# Battery_board_V4_0.net
KiCad netlist of a schematic drawn in EAGLE
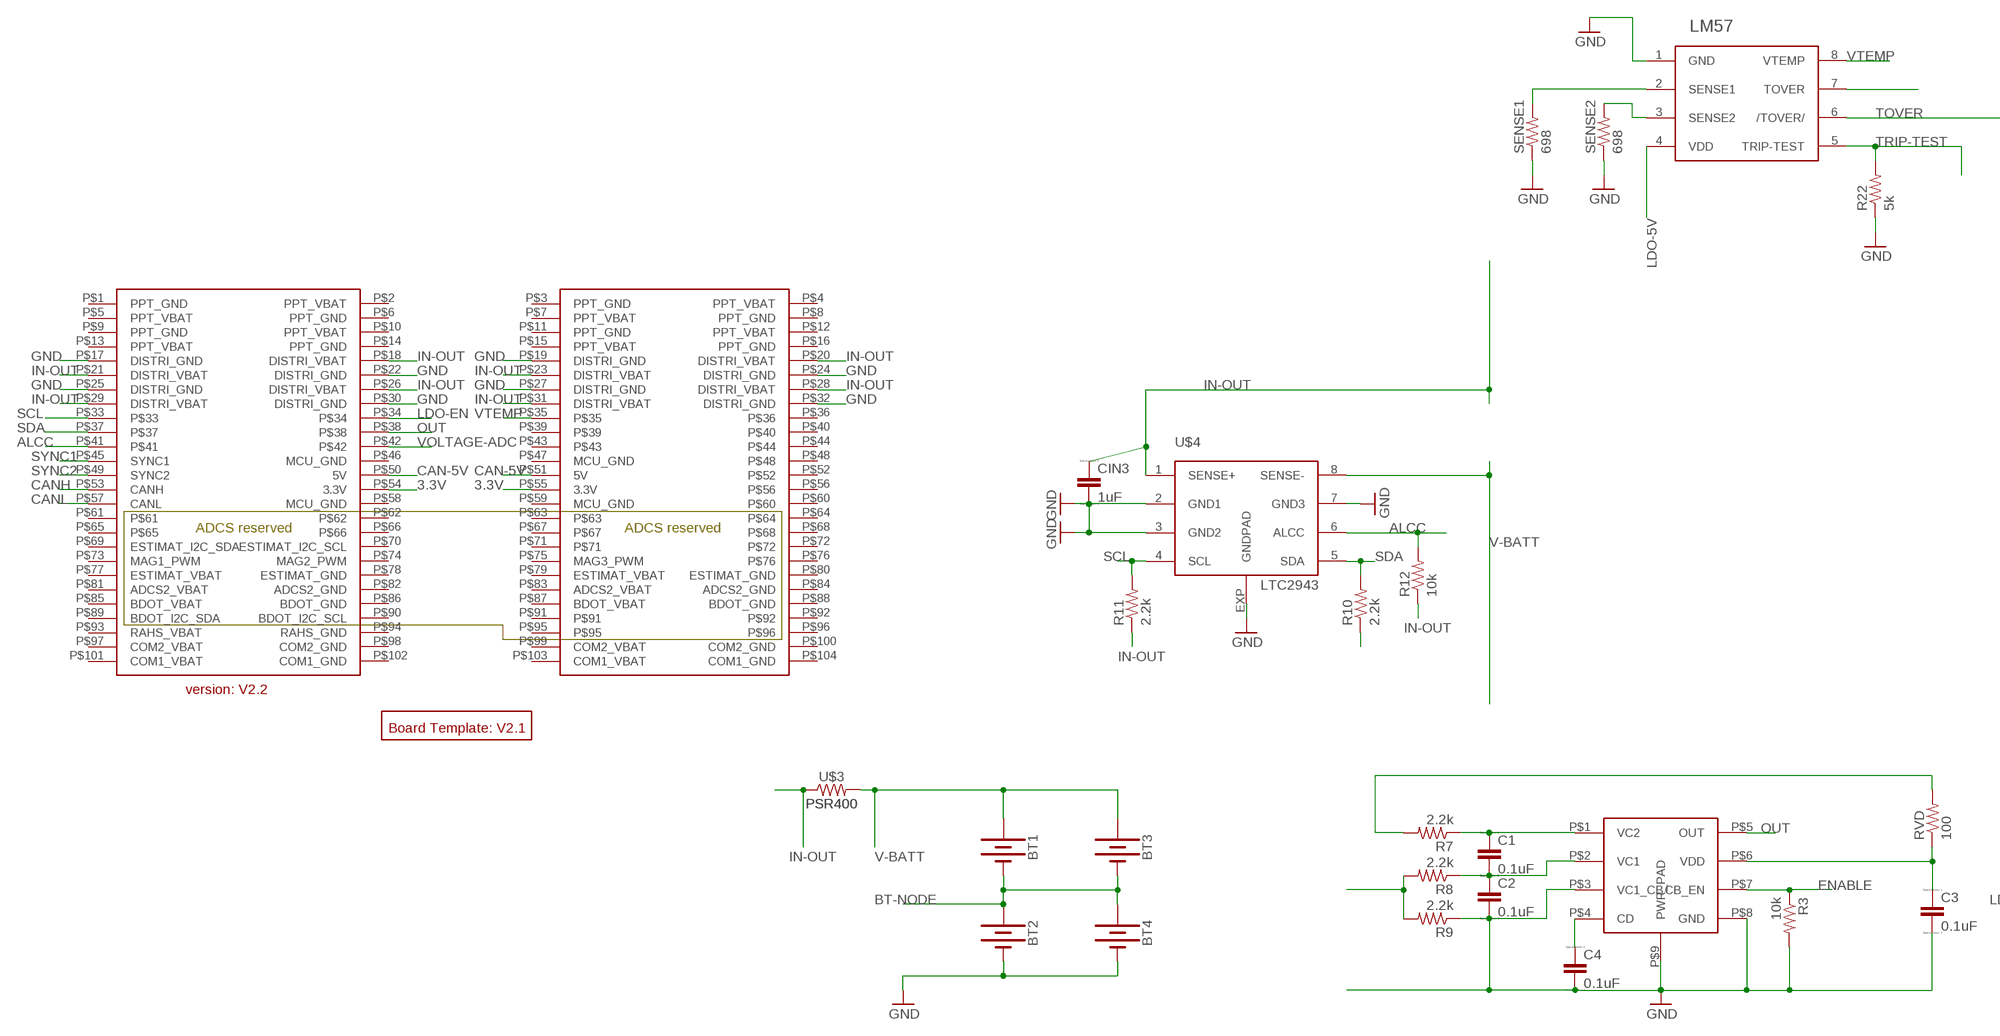
[diagram p0: schematic, sheet 1, part 1 of 2]
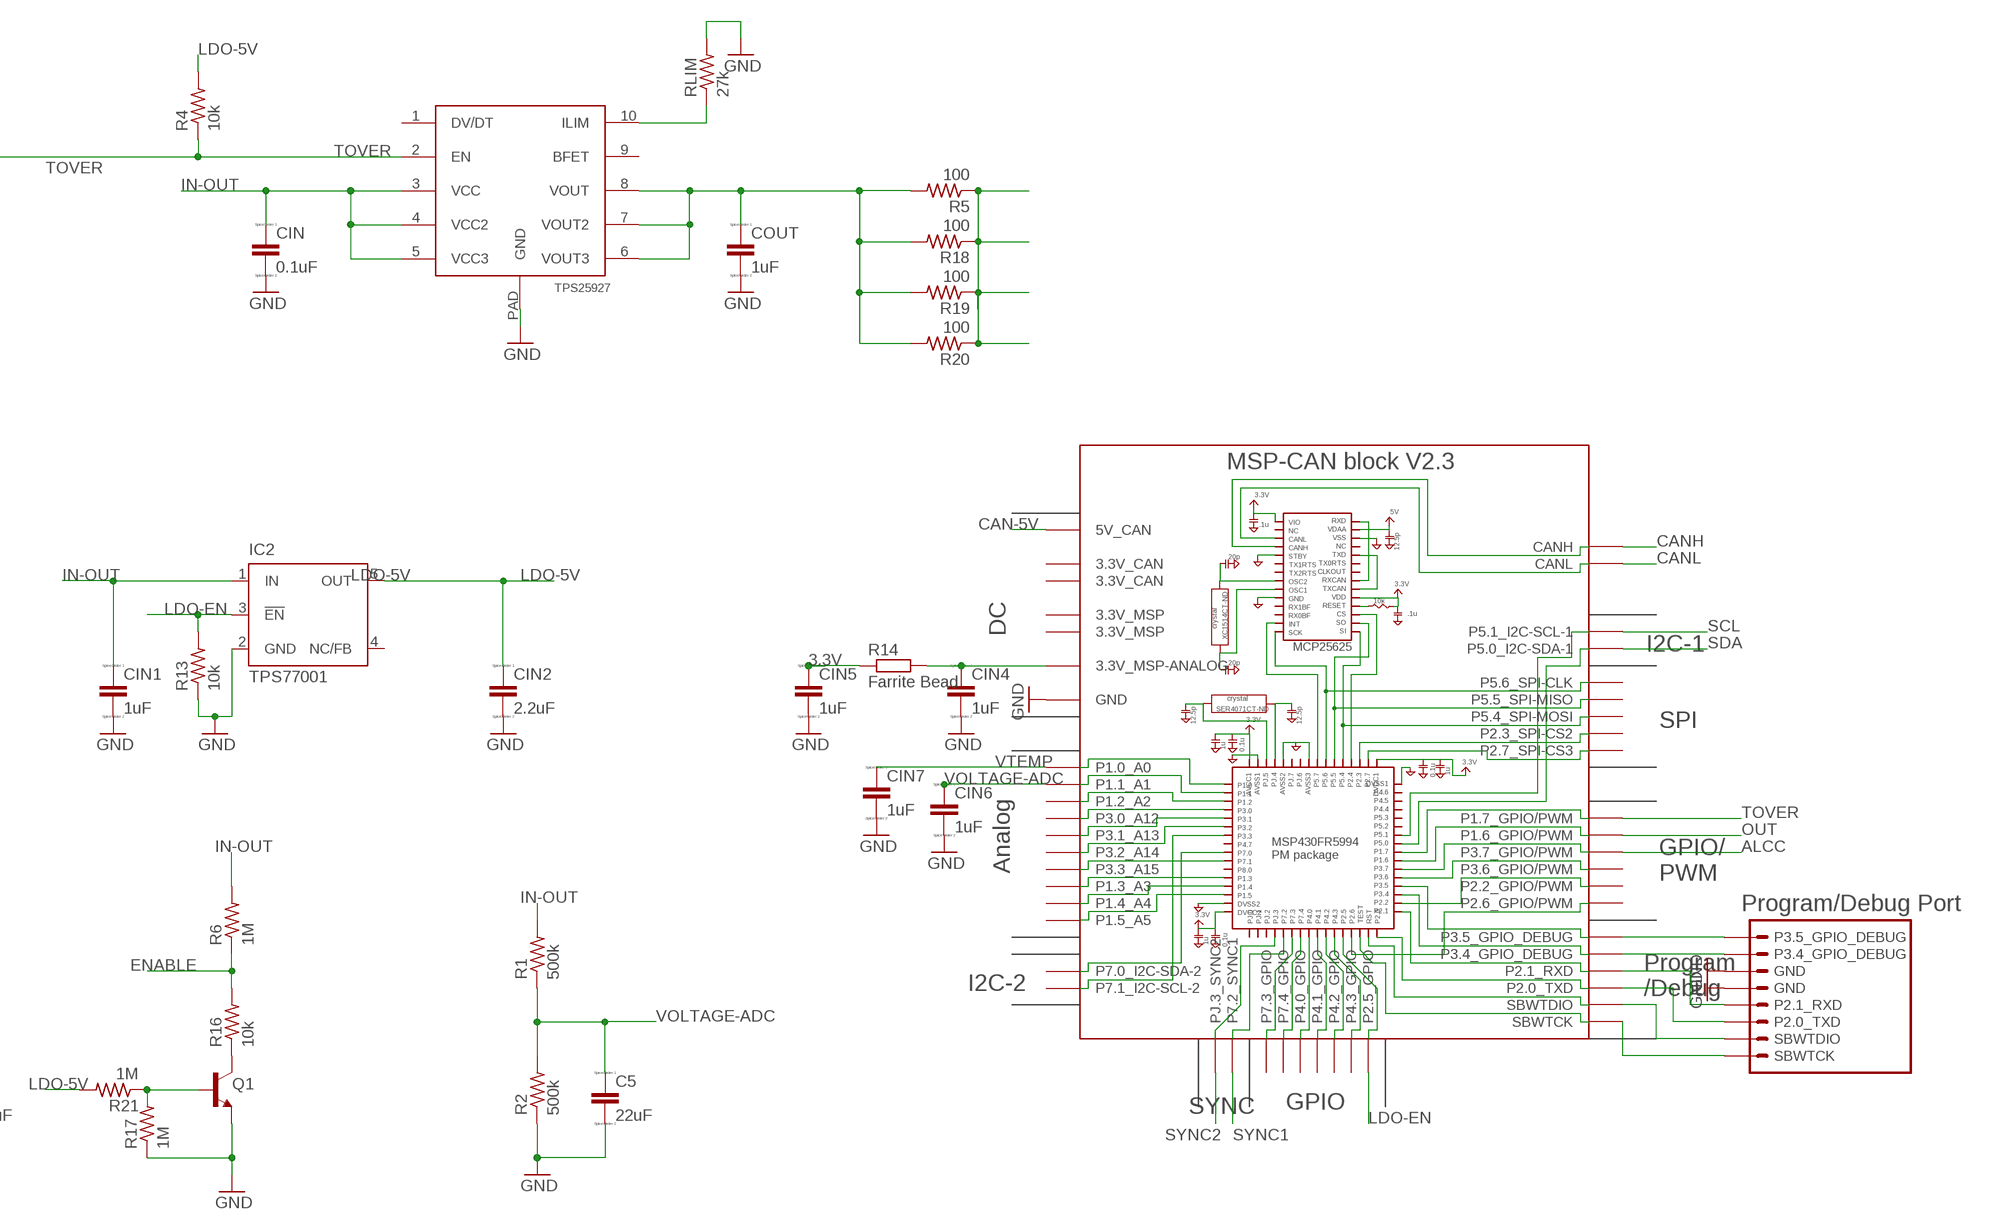
[diagram p1: schematic, sheet 1, part 2 of 2]

(export (version "E")
  (design (tool "Eeschema 10.0.6"))
  (components
    (comp (ref "BT1")
      (value "BATTERY-18650")
      (footprint "eagle-import:BATTERY_18650-HOLDER")
      (libsource (lib "eagle-import") (part "BATTERY-18650"))
    )
    (comp (ref "BT2")
      (value "BATTERY-18650")
      (footprint "eagle-import:BATTERY_18650-HOLDER")
      (libsource (lib "eagle-import") (part "BATTERY-18650"))
    )
    (comp (ref "BT3")
      (value "BATTERY-18650")
      (footprint "eagle-import:BATTERY_18650-HOLDER")
      (libsource (lib "eagle-import") (part "BATTERY-18650"))
    )
    (comp (ref "BT4")
      (value "BATTERY-18650")
      (footprint "eagle-import:BATTERY_18650-HOLDER")
      (libsource (lib "eagle-import") (part "BATTERY-18650"))
    )
    (comp (ref "C1")
      (value "0.1uF")
      (footprint "eagle-import:C0805")
      (libsource (lib "eagle-import") (part "C"))
    )
    (comp (ref "C2")
      (value "0.1uF")
      (footprint "eagle-import:C0805")
      (libsource (lib "eagle-import") (part "C"))
    )
    (comp (ref "C3")
      (value "0.1uF")
      (footprint "eagle-import:C0805")
      (libsource (lib "eagle-import") (part "C"))
    )
    (comp (ref "C4")
      (value "0.1uF")
      (footprint "eagle-import:C0805")
      (libsource (lib "eagle-import") (part "C"))
    )
    (comp (ref "C5")
      (value "22uF")
      (footprint "eagle-import:C1206")
      (libsource (lib "eagle-import") (part "CC1206"))
    )
    (comp (ref "CIN")
      (value "0.1uF")
      (footprint "eagle-import:C0805")
      (libsource (lib "eagle-import") (part "C"))
    )
    (comp (ref "CIN1")
      (value "1uF")
      (footprint "eagle-import:C0805")
      (libsource (lib "eagle-import") (part "C"))
    )
    (comp (ref "CIN2")
      (value "2.2uF")
      (footprint "eagle-import:C0805")
      (libsource (lib "eagle-import") (part "C"))
    )
    (comp (ref "CIN3")
      (value "1uF")
      (footprint "eagle-import:C0805")
      (libsource (lib "eagle-import") (part "C"))
    )
    (comp (ref "CIN4")
      (value "1uF")
      (footprint "eagle-import:C0805")
      (libsource (lib "eagle-import") (part "C"))
    )
    (comp (ref "CIN5")
      (value "1uF")
      (footprint "eagle-import:C0805")
      (libsource (lib "eagle-import") (part "C"))
    )
    (comp (ref "CIN6")
      (value "1uF")
      (footprint "eagle-import:C0805")
      (libsource (lib "eagle-import") (part "C"))
    )
    (comp (ref "CIN7")
      (value "1uF")
      (footprint "eagle-import:C0805")
      (libsource (lib "eagle-import") (part "C"))
    )
    (comp (ref "COUT")
      (value "1uF")
      (footprint "eagle-import:C0805")
      (libsource (lib "eagle-import") (part "C"))
    )
    (comp (ref "IC2")
      (value "TPS77001")
      (footprint "eagle-import:SOT23-DBV")
      (fields (field (name "MF") "TEXAS INSTRUMENTS") (field (name "MPN") "TPS77001DBVT"))
      (libsource (lib "eagle-import") (part "TPS77001"))
    )
    (comp (ref "Q1")
      (value "TRANS_NPN-MMBT2222AL")
      (footprint "eagle-import:SOT23-3")
      (libsource (lib "eagle-import") (part "TRANS_NPN-MMBT2222AL"))
    )
    (comp (ref "R1")
      (value "500k")
      (footprint "eagle-import:R0805")
      (libsource (lib "eagle-import") (part "R-US_R0805"))
    )
    (comp (ref "R2")
      (value "500k")
      (footprint "eagle-import:R0805")
      (libsource (lib "eagle-import") (part "R-US_R0805"))
    )
    (comp (ref "R3")
      (value "10k")
      (footprint "eagle-import:R0805")
      (libsource (lib "eagle-import") (part "R-US_R0805"))
    )
    (comp (ref "R4")
      (value "10k")
      (footprint "eagle-import:R0805")
      (libsource (lib "eagle-import") (part "R-US_R0805"))
    )
    (comp (ref "R5")
      (value "100")
      (footprint "eagle-import:R0805")
      (libsource (lib "eagle-import") (part "R-US_R0805"))
    )
    (comp (ref "R6")
      (value "1M")
      (footprint "eagle-import:R0805")
      (libsource (lib "eagle-import") (part "R-US_R0805"))
    )
    (comp (ref "R7")
      (value "2.2k")
      (footprint "eagle-import:R0805")
      (libsource (lib "eagle-import") (part "R-US_R0805"))
    )
    (comp (ref "R8")
      (value "2.2k")
      (footprint "eagle-import:R0805")
      (libsource (lib "eagle-import") (part "R-US_R0805"))
    )
    (comp (ref "R9")
      (value "2.2k")
      (footprint "eagle-import:R0805")
      (libsource (lib "eagle-import") (part "R-US_R0805"))
    )
    (comp (ref "R10")
      (value "2.2k")
      (footprint "eagle-import:R0805")
      (libsource (lib "eagle-import") (part "R-US_R0805"))
    )
    (comp (ref "R11")
      (value "2.2k")
      (footprint "eagle-import:R0805")
      (libsource (lib "eagle-import") (part "R-US_R0805"))
    )
    (comp (ref "R12")
      (value "10k")
      (footprint "eagle-import:R0805")
      (libsource (lib "eagle-import") (part "R-US_R0805"))
    )
    (comp (ref "R13")
      (value "10k")
      (footprint "eagle-import:R0805")
      (libsource (lib "eagle-import") (part "R-US_R0805"))
    )
    (comp (ref "R14")
      (value "Farrite Bead")
      (footprint "eagle-import:R1206")
      (libsource (lib "eagle-import") (part "R-EU_R1206"))
    )
    (comp (ref "R16")
      (value "10k")
      (footprint "eagle-import:R0805")
      (libsource (lib "eagle-import") (part "R-US_R0805"))
    )
    (comp (ref "R17")
      (value "1M")
      (footprint "eagle-import:M0805")
      (libsource (lib "eagle-import") (part "R-US_M0805"))
    )
    (comp (ref "R18")
      (value "100")
      (footprint "eagle-import:R0805")
      (libsource (lib "eagle-import") (part "R-US_R0805"))
    )
    (comp (ref "R19")
      (value "100")
      (footprint "eagle-import:R0805")
      (libsource (lib "eagle-import") (part "R-US_R0805"))
    )
    (comp (ref "R20")
      (value "100")
      (footprint "eagle-import:R0805")
      (libsource (lib "eagle-import") (part "R-US_R0805"))
    )
    (comp (ref "R21")
      (value "1M")
      (footprint "eagle-import:M0805")
      (libsource (lib "eagle-import") (part "R-US_M0805"))
    )
    (comp (ref "R22")
      (value "5k")
      (footprint "eagle-import:R0805")
      (libsource (lib "eagle-import") (part "R-US_R0805"))
    )
    (comp (ref "RLIM")
      (value "27k")
      (footprint "eagle-import:R0805")
      (libsource (lib "eagle-import") (part "R-US_R0805"))
    )
    (comp (ref "RVD")
      (value "100")
      (footprint "eagle-import:R0805")
      (libsource (lib "eagle-import") (part "R-US_R0805"))
    )
    (comp (ref "SENSE1")
      (value "698")
      (footprint "eagle-import:R0805")
      (libsource (lib "eagle-import") (part "R-US_R0805"))
    )
    (comp (ref "SENSE2")
      (value "698")
      (footprint "eagle-import:R0805")
      (libsource (lib "eagle-import") (part "R-US_R0805"))
    )
    (comp (ref "U$1")
      (value "MSP-CAN_BLOCK")
      (footprint "eagle-import:MSP-CAN_BLOCK")
      (libsource (lib "eagle-import") (part "MSP-CAN_BLOCK"))
    )
    (comp (ref "U$2")
      (value "PROGRAM/DEBUG_PORT")
      (footprint "eagle-import:1X08_CONNECTOR")
      (libsource (lib "eagle-import") (part "PROGRAM/DEBUG_PORT"))
    )
    (comp (ref "U$3")
      (value "PSR400")
      (footprint "eagle-import:PSR400")
      (libsource (lib "eagle-import") (part "PSR400"))
    )
    (comp (ref "U$4")
      (value "LTC2943")
      (footprint "eagle-import:DFN8(3X3)LT")
      (libsource (lib "eagle-import") (part "LTC2943"))
    )
    (comp (ref "U$5")
      (value "TPS252927")
      (footprint "eagle-import:VSON10")
      (libsource (lib "eagle-import") (part "TPS252927"))
    )
    (comp (ref "U$6")
      (value "LM57")
      (footprint "eagle-import:TSSOP-8")
      (libsource (lib "eagle-import") (part "LM57"))
    )
    (comp (ref "U$7")
      (value "2X26_CONNECTOR_(V2.2)")
      (footprint "eagle-import:4X26_CONNECTOR_(V2.2)")
      (libsource (lib "eagle-import") (part "2X26_CONNECTOR_(V2.2)"))
    )
    (comp (ref "U$8")
      (value "BQ29209")
      (footprint "eagle-import:VSON8")
      (libsource (lib "eagle-import") (part "BQ29209"))
    )
    (comp (ref "U$9")
      (value "BOARD_TEMPLATE_(V2.1)")
      (footprint "eagle-import:BOARD_TEMPLATE_(V2.1)")
      (libsource (lib "eagle-import") (part "BOARD_TEMPLATE_(V2.1)"))
    )
  )
  (nets
    (net (code "1") (name "/3.3V") (class "Default")
      (node (ref "CIN5") (pin "1") (pinfunction "1_1") (pintype "passive"))
      (node (ref "R14") (pin "1") (pinfunction "1_1") (pintype "passive"))
      (node (ref "U$7") (pin "P$54") (pinfunction "3.3V_P$54") (pintype "bidirectional"))
      (node (ref "U$7") (pin "P$55") (pinfunction "3.3V_P$55") (pintype "bidirectional"))
    )
    (net (code "2") (name "/ALCC") (class "Default")
      (node (ref "R12") (pin "2") (pinfunction "2_2") (pintype "passive"))
      (node (ref "U$1") (pin "P3.7_GPIO/PWM") (pinfunction "P3.7_GPIO/PWM_P3.7_GPIO/PWM") (pintype "bidirectional"))
      (node (ref "U$4") (pin "6") (pinfunction "ALCC_6") (pintype "bidirectional"))
      (node (ref "U$7") (pin "P$41") (pinfunction "P$41_P$41") (pintype "bidirectional"))
    )
    (net (code "3") (name "/BT-NODE") (class "Default")
      (node (ref "BT1") (pin "GND@1") (pinfunction "-_GND@1") (pintype "power_in"))
      (node (ref "BT2") (pin "PWR@1") (pinfunction "+_PWR@1") (pintype "power_in"))
      (node (ref "BT3") (pin "GND@1") (pinfunction "-_GND@1") (pintype "power_in"))
      (node (ref "BT4") (pin "PWR@1") (pinfunction "+_PWR@1") (pintype "power_in"))
      (node (ref "R8") (pin "2") (pinfunction "2_2") (pintype "passive"))
      (node (ref "R9") (pin "2") (pinfunction "2_2") (pintype "passive"))
    )
    (net (code "4") (name "/CAN-5V") (class "Default")
      (node (ref "U$1") (pin "5V") (pinfunction "5V_CAN_5V") (pintype "bidirectional"))
      (node (ref "U$7") (pin "P$50") (pinfunction "5V_P$50") (pintype "bidirectional"))
      (node (ref "U$7") (pin "P$51") (pinfunction "5V_P$51") (pintype "bidirectional"))
    )
    (net (code "5") (name "/CANH") (class "Default")
      (node (ref "U$1") (pin "CANH") (pinfunction "CANH_CANH") (pintype "bidirectional"))
      (node (ref "U$7") (pin "P$53") (pinfunction "CANH_P$53") (pintype "bidirectional"))
    )
    (net (code "6") (name "/CANL") (class "Default")
      (node (ref "U$1") (pin "CANL") (pinfunction "CANL_CANL") (pintype "bidirectional"))
      (node (ref "U$7") (pin "P$57") (pinfunction "CANL_P$57") (pintype "bidirectional"))
    )
    (net (code "7") (name "/ENABLE") (class "Default")
      (node (ref "R16") (pin "2") (pinfunction "2_2") (pintype "passive"))
      (node (ref "R3") (pin "1") (pinfunction "1_1") (pintype "passive"))
      (node (ref "R6") (pin "1") (pinfunction "1_1") (pintype "passive"))
      (node (ref "U$8") (pin "P$7") (pinfunction "CB_EN_P$7") (pintype "bidirectional"))
    )
    (net (code "8") (name "/IN-OUT") (class "Default")
      (node (ref "CIN") (pin "1") (pinfunction "1_1") (pintype "passive"))
      (node (ref "CIN1") (pin "1") (pinfunction "1_1") (pintype "passive"))
      (node (ref "CIN3") (pin "1") (pinfunction "1_1") (pintype "passive"))
      (node (ref "IC2") (pin "1") (pinfunction "IN_1") (pintype "input"))
      (node (ref "R1") (pin "2") (pinfunction "2_2") (pintype "passive"))
      (node (ref "R10") (pin "1") (pinfunction "1_1") (pintype "passive"))
      (node (ref "R11") (pin "1") (pinfunction "1_1") (pintype "passive"))
      (node (ref "R12") (pin "1") (pinfunction "1_1") (pintype "passive"))
      (node (ref "R6") (pin "2") (pinfunction "2_2") (pintype "passive"))
      (node (ref "U$3") (pin "P$1") (pinfunction "1_P$1") (pintype "passive"))
      (node (ref "U$4") (pin "1") (pinfunction "SENSE+_1") (pintype "bidirectional"))
      (node (ref "U$5") (pin "3") (pinfunction "VCC_3") (pintype "bidirectional"))
      (node (ref "U$5") (pin "4") (pinfunction "VCC2_4") (pintype "bidirectional"))
      (node (ref "U$5") (pin "5") (pinfunction "VCC3_5") (pintype "bidirectional"))
      (node (ref "U$7") (pin "P$18") (pinfunction "DISTRI_VBAT_P$18") (pintype "bidirectional"))
      (node (ref "U$7") (pin "P$20") (pinfunction "DISTRI_VBAT_P$20") (pintype "bidirectional"))
      (node (ref "U$7") (pin "P$21") (pinfunction "DISTRI_VBAT_P$21") (pintype "bidirectional"))
      (node (ref "U$7") (pin "P$23") (pinfunction "DISTRI_VBAT_P$23") (pintype "bidirectional"))
      (node (ref "U$7") (pin "P$26") (pinfunction "DISTRI_VBAT_P$26") (pintype "bidirectional"))
      (node (ref "U$7") (pin "P$28") (pinfunction "DISTRI_VBAT_P$28") (pintype "bidirectional"))
      (node (ref "U$7") (pin "P$29") (pinfunction "DISTRI_VBAT_P$29") (pintype "bidirectional"))
      (node (ref "U$7") (pin "P$31") (pinfunction "DISTRI_VBAT_P$31") (pintype "bidirectional"))
    )
    (net (code "9") (name "/LDO-5V") (class "Default")
      (node (ref "CIN2") (pin "1") (pinfunction "1_1") (pintype "passive"))
      (node (ref "IC2") (pin "5") (pinfunction "OUT_5") (pintype "passive"))
      (node (ref "R21") (pin "2") (pinfunction "2_2") (pintype "passive"))
      (node (ref "R4") (pin "2") (pinfunction "2_2") (pintype "passive"))
      (node (ref "U$6") (pin "4") (pinfunction "VDD_4") (pintype "bidirectional"))
    )
    (net (code "10") (name "/LDO-EN") (class "Default")
      (node (ref "IC2") (pin "3") (pinfunction "~{EN}_3") (pintype "input"))
      (node (ref "R13") (pin "2") (pinfunction "2_2") (pintype "passive"))
      (node (ref "U$1") (pin "P2.5_GPIO") (pinfunction "P2.5_GPIO_P2.5_GPIO") (pintype "bidirectional"))
      (node (ref "U$7") (pin "P$34") (pinfunction "P$34_P$34") (pintype "bidirectional"))
    )
    (net (code "11") (name "/OUT") (class "Default")
      (node (ref "U$1") (pin "P1.6_GPIO/PWM") (pinfunction "P1.6_GPIO/PWM_P1.6_GPIO/PWM") (pintype "bidirectional"))
      (node (ref "U$7") (pin "P$38") (pinfunction "P$38_P$38") (pintype "bidirectional"))
      (node (ref "U$8") (pin "P$5") (pinfunction "OUT_P$5") (pintype "bidirectional"))
    )
    (net (code "12") (name "/SCL") (class "Default")
      (node (ref "R11") (pin "2") (pinfunction "2_2") (pintype "passive"))
      (node (ref "U$1") (pin "P5.1_I2C-SCL-1") (pinfunction "P5.1_I2C-SCL-1_P5.1_I2C-SCL-1") (pintype "bidirectional"))
      (node (ref "U$4") (pin "4") (pinfunction "SCL_4") (pintype "bidirectional"))
      (node (ref "U$7") (pin "P$33") (pinfunction "P$33_P$33") (pintype "bidirectional"))
    )
    (net (code "13") (name "/SDA") (class "Default")
      (node (ref "R10") (pin "2") (pinfunction "2_2") (pintype "passive"))
      (node (ref "U$1") (pin "P5.0_I2C-SDA-1") (pinfunction "P5.0_I2C-SDA-1_P5.0_I2C-SDA-1") (pintype "bidirectional"))
      (node (ref "U$4") (pin "5") (pinfunction "SDA_5") (pintype "bidirectional"))
      (node (ref "U$7") (pin "P$37") (pinfunction "P$37_P$37") (pintype "bidirectional"))
    )
    (net (code "14") (name "/SYNC1") (class "Default")
      (node (ref "U$1") (pin "P7.2_SYNC1") (pinfunction "P7.2_SYNC1_P7.2_SYNC1") (pintype "bidirectional"))
      (node (ref "U$7") (pin "P$45") (pinfunction "SYNC1_P$45") (pintype "bidirectional"))
    )
    (net (code "15") (name "/SYNC2") (class "Default")
      (node (ref "U$1") (pin "PJ.3_SYNC2") (pinfunction "PJ.3_SYNC2_PJ.3_SYNC2") (pintype "bidirectional"))
      (node (ref "U$7") (pin "P$49") (pinfunction "SYNC2_P$49") (pintype "bidirectional"))
    )
    (net (code "16") (name "/TOVER") (class "Default")
      (node (ref "R4") (pin "1") (pinfunction "1_1") (pintype "passive"))
      (node (ref "U$1") (pin "P1.7_GPIO/PWM") (pinfunction "P1.7_GPIO/PWM_P1.7_GPIO/PWM") (pintype "bidirectional"))
      (node (ref "U$5") (pin "2") (pinfunction "EN_2") (pintype "bidirectional"))
      (node (ref "U$6") (pin "6") (pinfunction "/TOVER/_6") (pintype "bidirectional"))
    )
    (net (code "17") (name "/TRIP-TEST") (class "Default")
      (node (ref "R22") (pin "2") (pinfunction "2_2") (pintype "passive"))
      (node (ref "U$6") (pin "5") (pinfunction "TRIP-TEST_5") (pintype "bidirectional"))
    )
    (net (code "18") (name "/V-BATT") (class "Default")
      (node (ref "BT1") (pin "PWR@1") (pinfunction "+_PWR@1") (pintype "power_in"))
      (node (ref "BT3") (pin "PWR@1") (pinfunction "+_PWR@1") (pintype "power_in"))
      (node (ref "R7") (pin "2") (pinfunction "2_2") (pintype "passive"))
      (node (ref "RVD") (pin "2") (pinfunction "2_2") (pintype "passive"))
      (node (ref "U$3") (pin "P$2") (pinfunction "2_P$2") (pintype "passive"))
      (node (ref "U$4") (pin "8") (pinfunction "SENSE-_8") (pintype "bidirectional"))
    )
    (net (code "19") (name "/VOLTAGE-ADC") (class "Default")
      (node (ref "C5") (pin "1") (pinfunction "1_1") (pintype "passive"))
      (node (ref "CIN6") (pin "1") (pinfunction "1_1") (pintype "passive"))
      (node (ref "R1") (pin "1") (pinfunction "1_1") (pintype "passive"))
      (node (ref "R2") (pin "2") (pinfunction "2_2") (pintype "passive"))
      (node (ref "U$1") (pin "P1.1_A1") (pinfunction "P1.1_A1_P1.1_A1") (pintype "bidirectional"))
      (node (ref "U$7") (pin "P$42") (pinfunction "P$42_P$42") (pintype "bidirectional"))
    )
    (net (code "20") (name "/VTEMP") (class "Default")
      (node (ref "CIN7") (pin "1") (pinfunction "1_1") (pintype "passive"))
      (node (ref "U$1") (pin "P1.0_A0") (pinfunction "P1.0_A0_P1.0_A0") (pintype "bidirectional"))
      (node (ref "U$6") (pin "8") (pinfunction "VTEMP_8") (pintype "bidirectional"))
      (node (ref "U$7") (pin "P$35") (pinfunction "P$35_P$35") (pintype "bidirectional"))
    )
    (net (code "21") (name "GND") (class "Default")
      (node (ref "BT2") (pin "GND@1") (pinfunction "-_GND@1") (pintype "power_in"))
      (node (ref "BT4") (pin "GND@1") (pinfunction "-_GND@1") (pintype "power_in"))
      (node (ref "C2") (pin "2") (pinfunction "2_2") (pintype "passive"))
      (node (ref "C3") (pin "2") (pinfunction "2_2") (pintype "passive"))
      (node (ref "C4") (pin "2") (pinfunction "2_2") (pintype "passive"))
      (node (ref "C5") (pin "2") (pinfunction "2_2") (pintype "passive"))
      (node (ref "CIN") (pin "2") (pinfunction "2_2") (pintype "passive"))
      (node (ref "CIN1") (pin "2") (pinfunction "2_2") (pintype "passive"))
      (node (ref "CIN2") (pin "2") (pinfunction "2_2") (pintype "passive"))
      (node (ref "CIN3") (pin "2") (pinfunction "2_2") (pintype "passive"))
      (node (ref "CIN4") (pin "2") (pinfunction "2_2") (pintype "passive"))
      (node (ref "CIN5") (pin "2") (pinfunction "2_2") (pintype "passive"))
      (node (ref "CIN6") (pin "2") (pinfunction "2_2") (pintype "passive"))
      (node (ref "CIN7") (pin "2") (pinfunction "2_2") (pintype "passive"))
      (node (ref "COUT") (pin "2") (pinfunction "2_2") (pintype "passive"))
      (node (ref "IC2") (pin "2") (pinfunction "GND_2") (pintype "power_in"))
      (node (ref "Q1") (pin "2") (pinfunction "E_2") (pintype "passive"))
      (node (ref "R13") (pin "1") (pinfunction "1_1") (pintype "passive"))
      (node (ref "R17") (pin "1") (pinfunction "1_1") (pintype "passive"))
      (node (ref "R2") (pin "1") (pinfunction "1_1") (pintype "passive"))
      (node (ref "R22") (pin "1") (pinfunction "1_1") (pintype "passive"))
      (node (ref "R3") (pin "2") (pinfunction "2_2") (pintype "passive"))
      (node (ref "R9") (pin "1") (pinfunction "1_1") (pintype "passive"))
      (node (ref "RLIM") (pin "2") (pinfunction "2_2") (pintype "passive"))
      (node (ref "SENSE1") (pin "1") (pinfunction "1_1") (pintype "passive"))
      (node (ref "SENSE2") (pin "1") (pinfunction "1_1") (pintype "passive"))
      (node (ref "U$1") (pin "GND@1") (pinfunction "GND_GND@1") (pintype "bidirectional"))
      (node (ref "U$1") (pin "GND@10") (pinfunction "GND_GND@10") (pintype "bidirectional"))
      (node (ref "U$1") (pin "GND@11") (pinfunction "GND_GND@11") (pintype "bidirectional"))
      (node (ref "U$1") (pin "GND@12") (pinfunction "GND_GND@12") (pintype "bidirectional"))
      (node (ref "U$1") (pin "GND@13") (pinfunction "GND_GND@13") (pintype "bidirectional"))
      (node (ref "U$1") (pin "GND@14") (pinfunction "GND_GND@14") (pintype "bidirectional"))
      (node (ref "U$1") (pin "GND@15") (pinfunction "GND_GND@15") (pintype "bidirectional"))
      (node (ref "U$1") (pin "GND@16") (pinfunction "GND_GND@16") (pintype "bidirectional"))
      (node (ref "U$1") (pin "GND@17") (pinfunction "GND_GND@17") (pintype "bidirectional"))
      (node (ref "U$1") (pin "GND@2") (pinfunction "GND_GND@2") (pintype "bidirectional"))
      (node (ref "U$1") (pin "GND@26") (pinfunction "GND_GND@26") (pintype "bidirectional"))
      (node (ref "U$1") (pin "GND@3") (pinfunction "GND_GND@3") (pintype "bidirectional"))
      (node (ref "U$1") (pin "GND@4") (pinfunction "GND_GND@4") (pintype "bidirectional"))
      (node (ref "U$1") (pin "GND@5") (pinfunction "GND_GND@5") (pintype "bidirectional"))
      (node (ref "U$1") (pin "GND@7") (pinfunction "GND_GND@7") (pintype "bidirectional"))
      (node (ref "U$1") (pin "GND@8") (pinfunction "GND_GND@8") (pintype "bidirectional"))
      (node (ref "U$1") (pin "GND@9") (pinfunction "GND_GND@9") (pintype "bidirectional"))
      (node (ref "U$2") (pin "5") (pinfunction "GND_5") (pintype "bidirectional"))
      (node (ref "U$2") (pin "6") (pinfunction "GND_6") (pintype "bidirectional"))
      (node (ref "U$4") (pin "2") (pinfunction "GND1_2") (pintype "bidirectional"))
      (node (ref "U$4") (pin "3") (pinfunction "GND2_3") (pintype "bidirectional"))
      (node (ref "U$4") (pin "7") (pinfunction "GND3_7") (pintype "bidirectional"))
      (node (ref "U$4") (pin "EXP") (pinfunction "GNDPAD_EXP") (pintype "bidirectional"))
      (node (ref "U$5") (pin "PAD") (pinfunction "GND_PAD") (pintype "bidirectional"))
      (node (ref "U$6") (pin "1") (pinfunction "GND_1") (pintype "bidirectional"))
      (node (ref "U$7") (pin "P$17") (pinfunction "DISTRI_GND_P$17") (pintype "bidirectional"))
      (node (ref "U$7") (pin "P$19") (pinfunction "DISTRI_GND_P$19") (pintype "bidirectional"))
      (node (ref "U$7") (pin "P$22") (pinfunction "DISTRI_GND_P$22") (pintype "bidirectional"))
      (node (ref "U$7") (pin "P$24") (pinfunction "DISTRI_GND_P$24") (pintype "bidirectional"))
      (node (ref "U$7") (pin "P$25") (pinfunction "DISTRI_GND_P$25") (pintype "bidirectional"))
      (node (ref "U$7") (pin "P$27") (pinfunction "DISTRI_GND_P$27") (pintype "bidirectional"))
      (node (ref "U$7") (pin "P$30") (pinfunction "DISTRI_GND_P$30") (pintype "bidirectional"))
      (node (ref "U$7") (pin "P$32") (pinfunction "DISTRI_GND_P$32") (pintype "bidirectional"))
      (node (ref "U$8") (pin "P$3") (pinfunction "VC1_CB_P$3") (pintype "bidirectional"))
      (node (ref "U$8") (pin "P$8") (pinfunction "GND_P$8") (pintype "bidirectional"))
      (node (ref "U$8") (pin "P$9") (pinfunction "PWR_PAD_P$9") (pintype "bidirectional"))
    )
    (net (code "22") (name "Net-(Q1-B)") (class "Default")
      (node (ref "Q1") (pin "1") (pinfunction "B_1") (pintype "passive"))
      (node (ref "R17") (pin "2") (pinfunction "2_2") (pintype "passive"))
      (node (ref "R21") (pin "1") (pinfunction "1_1") (pintype "passive"))
    )
    (net (code "23") (name "Net-(Q1-C)") (class "Default")
      (node (ref "Q1") (pin "3") (pinfunction "C_3") (pintype "passive"))
      (node (ref "R16") (pin "1") (pinfunction "1_1") (pintype "passive"))
    )
    (net (code "24") (name "Net-(R18-Pad1)") (class "Default")
      (node (ref "R18") (pin "1") (pinfunction "1_1") (pintype "passive"))
      (node (ref "R19") (pin "1") (pinfunction "1_1") (pintype "passive"))
      (node (ref "R20") (pin "1") (pinfunction "1_1") (pintype "passive"))
      (node (ref "R5") (pin "1") (pinfunction "1_1") (pintype "passive"))
    )
    (net (code "25") (name "Net-(U$1-3.3V_MSP-ANALOG)") (class "Default")
      (node (ref "CIN4") (pin "1") (pinfunction "1_1") (pintype "passive"))
      (node (ref "R14") (pin "2") (pinfunction "2_2") (pintype "passive"))
      (node (ref "U$1") (pin "3.3V_ANALOG@MSP2") (pinfunction "3.3V_MSP-ANALOG_3.3V_ANALOG@MSP2") (pintype "bidirectional"))
    )
    (net (code "26") (name "Net-(U$1-PadSBWTCK)") (class "Default")
      (node (ref "U$1") (pin "SBWTCK") (pinfunction "SBWTCK_SBWTCK") (pintype "bidirectional"))
      (node (ref "U$2") (pin "SBWTCK") (pinfunction "SBWTCK_SBWTCK") (pintype "bidirectional"))
    )
    (net (code "27") (name "Net-(U$2-P2.0_TXD)") (class "Default")
      (node (ref "U$1") (pin "P2.0_TXD") (pinfunction "P2.0_TXD_P2.0_TXD") (pintype "bidirectional"))
      (node (ref "U$2") (pin "3") (pinfunction "P2.0_TXD_3") (pintype "bidirectional"))
    )
    (net (code "28") (name "Net-(U$2-P2.1_RXD)") (class "Default")
      (node (ref "U$1") (pin "P2.1_RXD") (pinfunction "P2.1_RXD_P2.1_RXD") (pintype "bidirectional"))
      (node (ref "U$2") (pin "4") (pinfunction "P2.1_RXD_4") (pintype "bidirectional"))
    )
    (net (code "29") (name "Net-(U$2-P3.4_GPIO_DEBUG)") (class "Default")
      (node (ref "U$1") (pin "P3.4_GPIO_DEBUG") (pinfunction "P3.4_GPIO_DEBUG_P3.4_GPIO_DEBUG") (pintype "bidirectional"))
      (node (ref "U$2") (pin "7") (pinfunction "P3.4_GPIO_DEBUG_7") (pintype "bidirectional"))
    )
    (net (code "30") (name "Net-(U$2-P3.5_GPIO_DEBUG)") (class "Default")
      (node (ref "U$1") (pin "P3.5_GPIO_DEBUG") (pinfunction "P3.5_GPIO_DEBUG_P3.5_GPIO_DEBUG") (pintype "bidirectional"))
      (node (ref "U$2") (pin "8") (pinfunction "P3.5_GPIO_DEBUG_8") (pintype "bidirectional"))
    )
    (net (code "31") (name "Net-(U$2-SBWTDIO)") (class "Default")
      (node (ref "U$1") (pin "SBWTDIO") (pinfunction "SBWTDIO_SBWTDIO") (pintype "bidirectional"))
      (node (ref "U$2") (pin "2") (pinfunction "SBWTDIO_2") (pintype "bidirectional"))
    )
    (net (code "32") (name "Net-(U$5-ILIM)") (class "Default")
      (node (ref "RLIM") (pin "1") (pinfunction "1_1") (pintype "passive"))
      (node (ref "U$5") (pin "10") (pinfunction "ILIM_10") (pintype "bidirectional"))
    )
    (net (code "33") (name "Net-(U$5-VOUT)") (class "Default")
      (node (ref "COUT") (pin "1") (pinfunction "1_1") (pintype "passive"))
      (node (ref "R18") (pin "2") (pinfunction "2_2") (pintype "passive"))
      (node (ref "R19") (pin "2") (pinfunction "2_2") (pintype "passive"))
      (node (ref "R20") (pin "2") (pinfunction "2_2") (pintype "passive"))
      (node (ref "R5") (pin "2") (pinfunction "2_2") (pintype "passive"))
      (node (ref "U$5") (pin "6") (pinfunction "VOUT3_6") (pintype "bidirectional"))
      (node (ref "U$5") (pin "7") (pinfunction "VOUT2_7") (pintype "bidirectional"))
      (node (ref "U$5") (pin "8") (pinfunction "VOUT_8") (pintype "bidirectional"))
    )
    (net (code "34") (name "Net-(U$6-SENSE1)") (class "Default")
      (node (ref "SENSE1") (pin "2") (pinfunction "2_2") (pintype "passive"))
      (node (ref "U$6") (pin "2") (pinfunction "SENSE1_2") (pintype "bidirectional"))
    )
    (net (code "35") (name "Net-(U$6-SENSE2)") (class "Default")
      (node (ref "SENSE2") (pin "2") (pinfunction "2_2") (pintype "passive"))
      (node (ref "U$6") (pin "3") (pinfunction "SENSE2_3") (pintype "bidirectional"))
    )
    (net (code "36") (name "Net-(U$8-CD)") (class "Default")
      (node (ref "C4") (pin "1") (pinfunction "1_1") (pintype "passive"))
      (node (ref "U$8") (pin "P$4") (pinfunction "CD_P$4") (pintype "bidirectional"))
    )
    (net (code "37") (name "Net-(U$8-VC1)") (class "Default")
      (node (ref "C1") (pin "2") (pinfunction "2_2") (pintype "passive"))
      (node (ref "C2") (pin "1") (pinfunction "1_1") (pintype "passive"))
      (node (ref "R8") (pin "1") (pinfunction "1_1") (pintype "passive"))
      (node (ref "U$8") (pin "P$2") (pinfunction "VC1_P$2") (pintype "bidirectional"))
    )
    (net (code "38") (name "Net-(U$8-VC2)") (class "Default")
      (node (ref "C1") (pin "1") (pinfunction "1_1") (pintype "passive"))
      (node (ref "R7") (pin "1") (pinfunction "1_1") (pintype "passive"))
      (node (ref "U$8") (pin "P$1") (pinfunction "VC2_P$1") (pintype "bidirectional"))
    )
    (net (code "39") (name "Net-(U$8-VDD)") (class "Default")
      (node (ref "C3") (pin "1") (pinfunction "1_1") (pintype "passive"))
      (node (ref "RVD") (pin "1") (pinfunction "1_1") (pintype "passive"))
      (node (ref "U$8") (pin "P$6") (pinfunction "VDD_P$6") (pintype "bidirectional"))
    )
    (net (code "40") (name "unconnected-(IC2-NC{slash}FB-Pad4)") (class "Default")
      (node (ref "IC2") (pin "4") (pinfunction "NC/FB_4") (pintype "passive"))
    )
    (net (code "41") (name "unconnected-(U$1-3.3V_CAN-Pad3.3V@CAN1)") (class "Default")
      (node (ref "U$1") (pin "3.3V@CAN1") (pinfunction "3.3V_CAN_3.3V@CAN1") (pintype "bidirectional"))
    )
    (net (code "42") (name "unconnected-(U$1-3.3V_CAN-Pad3.3V@CAN2)") (class "Default")
      (node (ref "U$1") (pin "3.3V@CAN2") (pinfunction "3.3V_CAN_3.3V@CAN2") (pintype "bidirectional"))
    )
    (net (code "43") (name "unconnected-(U$1-3.3V_MSP-Pad3.3V@MSP1)") (class "Default")
      (node (ref "U$1") (pin "3.3V@MSP1") (pinfunction "3.3V_MSP_3.3V@MSP1") (pintype "bidirectional"))
    )
    (net (code "44") (name "unconnected-(U$1-3.3V_MSP-Pad3.3V@MSP2)") (class "Default")
      (node (ref "U$1") (pin "3.3V@MSP2") (pinfunction "3.3V_MSP_3.3V@MSP2") (pintype "bidirectional"))
    )
    (net (code "45") (name "unconnected-(U$1-P2.3_SPI-CS2-PadP2.4_SPI-CS2)") (class "Default")
      (node (ref "U$1") (pin "P2.4_SPI-CS2") (pinfunction "P2.3_SPI-CS2_P2.4_SPI-CS2") (pintype "bidirectional"))
    )
    (net (code "46") (name "unconnected-(U$1-PadP1.2_A2)") (class "Default")
      (node (ref "U$1") (pin "P1.2_A2") (pinfunction "P1.2_A2_P1.2_A2") (pintype "bidirectional"))
    )
    (net (code "47") (name "unconnected-(U$1-PadP1.3_A3)") (class "Default")
      (node (ref "U$1") (pin "P1.3_A3") (pinfunction "P1.3_A3_P1.3_A3") (pintype "bidirectional"))
    )
    (net (code "48") (name "unconnected-(U$1-PadP1.4_A4)") (class "Default")
      (node (ref "U$1") (pin "P1.4_A4") (pinfunction "P1.4_A4_P1.4_A4") (pintype "bidirectional"))
    )
    (net (code "49") (name "unconnected-(U$1-PadP1.5_A5)") (class "Default")
      (node (ref "U$1") (pin "P1.5_A5") (pinfunction "P1.5_A5_P1.5_A5") (pintype "bidirectional"))
    )
    (net (code "50") (name "unconnected-(U$1-PadP2.2_GPIO{slash}PWM)") (class "Default")
      (node (ref "U$1") (pin "P2.2_GPIO/PWM") (pinfunction "P2.2_GPIO/PWM_P2.2_GPIO/PWM") (pintype "bidirectional"))
    )
    (net (code "51") (name "unconnected-(U$1-PadP2.6_GPIO{slash}PWM)") (class "Default")
      (node (ref "U$1") (pin "P2.6_GPIO/PWM") (pinfunction "P2.6_GPIO/PWM_P2.6_GPIO/PWM") (pintype "bidirectional"))
    )
    (net (code "52") (name "unconnected-(U$1-PadP2.7_SPI-CS3)") (class "Default")
      (node (ref "U$1") (pin "P2.7_SPI-CS3") (pinfunction "P2.7_SPI-CS3_P2.7_SPI-CS3") (pintype "bidirectional"))
    )
    (net (code "53") (name "unconnected-(U$1-PadP3.0_A12)") (class "Default")
      (node (ref "U$1") (pin "P3.0_A12") (pinfunction "P3.0_A12_P3.0_A12") (pintype "bidirectional"))
    )
    (net (code "54") (name "unconnected-(U$1-PadP3.1_A13)") (class "Default")
      (node (ref "U$1") (pin "P3.1_A13") (pinfunction "P3.1_A13_P3.1_A13") (pintype "bidirectional"))
    )
    (net (code "55") (name "unconnected-(U$1-PadP3.2_A14)") (class "Default")
      (node (ref "U$1") (pin "P3.2_A14") (pinfunction "P3.2_A14_P3.2_A14") (pintype "bidirectional"))
    )
    (net (code "56") (name "unconnected-(U$1-PadP3.3_A15)") (class "Default")
      (node (ref "U$1") (pin "P3.3_A15") (pinfunction "P3.3_A15_P3.3_A15") (pintype "bidirectional"))
    )
    (net (code "57") (name "unconnected-(U$1-PadP3.6_GPIO{slash}PWM)") (class "Default")
      (node (ref "U$1") (pin "P3.6_GPIO/PWM") (pinfunction "P3.6_GPIO/PWM_P3.6_GPIO/PWM") (pintype "bidirectional"))
    )
    (net (code "58") (name "unconnected-(U$1-PadP4.0_GPIO)") (class "Default")
      (node (ref "U$1") (pin "P4.0_GPIO") (pinfunction "P4.0_GPIO_P4.0_GPIO") (pintype "bidirectional"))
    )
    (net (code "59") (name "unconnected-(U$1-PadP4.1_GPIO)") (class "Default")
      (node (ref "U$1") (pin "P4.1_GPIO") (pinfunction "P4.1_GPIO_P4.1_GPIO") (pintype "bidirectional"))
    )
    (net (code "60") (name "unconnected-(U$1-PadP4.2_GPIO)") (class "Default")
      (node (ref "U$1") (pin "P4.2_GPIO") (pinfunction "P4.2_GPIO_P4.2_GPIO") (pintype "bidirectional"))
    )
    (net (code "61") (name "unconnected-(U$1-PadP4.3_GPIO)") (class "Default")
      (node (ref "U$1") (pin "P4.3_GPIO") (pinfunction "P4.3_GPIO_P4.3_GPIO") (pintype "bidirectional"))
    )
    (net (code "62") (name "unconnected-(U$1-PadP5.4_SPI-MOSI)") (class "Default")
      (node (ref "U$1") (pin "P5.4_SPI-MOSI") (pinfunction "P5.4_SPI-MOSI_P5.4_SPI-MOSI") (pintype "bidirectional"))
    )
    (net (code "63") (name "unconnected-(U$1-PadP5.5_SPI-MISO)") (class "Default")
      (node (ref "U$1") (pin "P5.5_SPI-MISO") (pinfunction "P5.5_SPI-MISO_P5.5_SPI-MISO") (pintype "bidirectional"))
    )
    (net (code "64") (name "unconnected-(U$1-PadP5.6_SPI-CLK)") (class "Default")
      (node (ref "U$1") (pin "P5.6_SPI-CLK") (pinfunction "P5.6_SPI-CLK_P5.6_SPI-CLK") (pintype "bidirectional"))
    )
    (net (code "65") (name "unconnected-(U$1-PadP7.0_I2C-SDA-2)") (class "Default")
      (node (ref "U$1") (pin "P7.0_I2C-SDA-2") (pinfunction "P7.0_I2C-SDA-2_P7.0_I2C-SDA-2") (pintype "bidirectional"))
    )
    (net (code "66") (name "unconnected-(U$1-PadP7.1_I2C-SCL-2)") (class "Default")
      (node (ref "U$1") (pin "P7.1_I2C-SCL-2") (pinfunction "P7.1_I2C-SCL-2_P7.1_I2C-SCL-2") (pintype "bidirectional"))
    )
    (net (code "67") (name "unconnected-(U$1-PadP7.3_GPIO)") (class "Default")
      (node (ref "U$1") (pin "P7.3_GPIO") (pinfunction "P7.3_GPIO_P7.3_GPIO") (pintype "bidirectional"))
    )
    (net (code "68") (name "unconnected-(U$1-PadP7.4_GPIO)") (class "Default")
      (node (ref "U$1") (pin "P7.4_GPIO") (pinfunction "P7.4_GPIO_P7.4_GPIO") (pintype "bidirectional"))
    )
    (net (code "69") (name "unconnected-(U$5-BFET-Pad9)") (class "Default")
      (node (ref "U$5") (pin "9") (pinfunction "BFET_9") (pintype "bidirectional"))
    )
    (net (code "70") (name "unconnected-(U$5-DV{slash}DT-Pad1)") (class "Default")
      (node (ref "U$5") (pin "1") (pinfunction "DV/DT_1") (pintype "bidirectional"))
    )
    (net (code "71") (name "unconnected-(U$6-TOVER-Pad7)") (class "Default")
      (node (ref "U$6") (pin "7") (pinfunction "TOVER_7") (pintype "bidirectional"))
    )
    (net (code "72") (name "unconnected-(U$7-ADCS2_GND-PadP$82)") (class "Default")
      (node (ref "U$7") (pin "P$82") (pinfunction "ADCS2_GND_P$82") (pintype "bidirectional"))
    )
    (net (code "73") (name "unconnected-(U$7-ADCS2_GND-PadP$84)") (class "Default")
      (node (ref "U$7") (pin "P$84") (pinfunction "ADCS2_GND_P$84") (pintype "bidirectional"))
    )
    (net (code "74") (name "unconnected-(U$7-ADCS2_VBAT-PadP$81)") (class "Default")
      (node (ref "U$7") (pin "P$81") (pinfunction "ADCS2_VBAT_P$81") (pintype "bidirectional"))
    )
    (net (code "75") (name "unconnected-(U$7-ADCS2_VBAT-PadP$83)") (class "Default")
      (node (ref "U$7") (pin "P$83") (pinfunction "ADCS2_VBAT_P$83") (pintype "bidirectional"))
    )
    (net (code "76") (name "unconnected-(U$7-BDOT_GND-PadP$86)") (class "Default")
      (node (ref "U$7") (pin "P$86") (pinfunction "BDOT_GND_P$86") (pintype "bidirectional"))
    )
    (net (code "77") (name "unconnected-(U$7-BDOT_GND-PadP$88)") (class "Default")
      (node (ref "U$7") (pin "P$88") (pinfunction "BDOT_GND_P$88") (pintype "bidirectional"))
    )
    (net (code "78") (name "unconnected-(U$7-BDOT_I2C_SCL-PadP$90)") (class "Default")
      (node (ref "U$7") (pin "P$90") (pinfunction "BDOT_I2C_SCL_P$90") (pintype "bidirectional"))
    )
    (net (code "79") (name "unconnected-(U$7-BDOT_I2C_SDA-PadP$89)") (class "Default")
      (node (ref "U$7") (pin "P$89") (pinfunction "BDOT_I2C_SDA_P$89") (pintype "bidirectional"))
    )
    (net (code "80") (name "unconnected-(U$7-BDOT_VBAT-PadP$85)") (class "Default")
      (node (ref "U$7") (pin "P$85") (pinfunction "BDOT_VBAT_P$85") (pintype "bidirectional"))
    )
    (net (code "81") (name "unconnected-(U$7-BDOT_VBAT-PadP$87)") (class "Default")
      (node (ref "U$7") (pin "P$87") (pinfunction "BDOT_VBAT_P$87") (pintype "bidirectional"))
    )
    (net (code "82") (name "unconnected-(U$7-COM1_GND-PadP$102)") (class "Default")
      (node (ref "U$7") (pin "P$102") (pinfunction "COM1_GND_P$102") (pintype "bidirectional"))
    )
    (net (code "83") (name "unconnected-(U$7-COM1_GND-PadP$104)") (class "Default")
      (node (ref "U$7") (pin "P$104") (pinfunction "COM1_GND_P$104") (pintype "bidirectional"))
    )
    (net (code "84") (name "unconnected-(U$7-COM1_VBAT-PadP$101)") (class "Default")
      (node (ref "U$7") (pin "P$101") (pinfunction "COM1_VBAT_P$101") (pintype "bidirectional"))
    )
    (net (code "85") (name "unconnected-(U$7-COM1_VBAT-PadP$103)") (class "Default")
      (node (ref "U$7") (pin "P$103") (pinfunction "COM1_VBAT_P$103") (pintype "bidirectional"))
    )
    (net (code "86") (name "unconnected-(U$7-COM2_GND-PadP$98)") (class "Default")
      (node (ref "U$7") (pin "P$98") (pinfunction "COM2_GND_P$98") (pintype "bidirectional"))
    )
    (net (code "87") (name "unconnected-(U$7-COM2_GND-PadP$100)") (class "Default")
      (node (ref "U$7") (pin "P$100") (pinfunction "COM2_GND_P$100") (pintype "bidirectional"))
    )
    (net (code "88") (name "unconnected-(U$7-COM2_VBAT-PadP$97)") (class "Default")
      (node (ref "U$7") (pin "P$97") (pinfunction "COM2_VBAT_P$97") (pintype "bidirectional"))
    )
    (net (code "89") (name "unconnected-(U$7-COM2_VBAT-PadP$99)") (class "Default")
      (node (ref "U$7") (pin "P$99") (pinfunction "COM2_VBAT_P$99") (pintype "bidirectional"))
    )
    (net (code "90") (name "unconnected-(U$7-ESTIMAT_GND-PadP$78)") (class "Default")
      (node (ref "U$7") (pin "P$78") (pinfunction "ESTIMAT_GND_P$78") (pintype "bidirectional"))
    )
    (net (code "91") (name "unconnected-(U$7-ESTIMAT_GND-PadP$80)") (class "Default")
      (node (ref "U$7") (pin "P$80") (pinfunction "ESTIMAT_GND_P$80") (pintype "bidirectional"))
    )
    (net (code "92") (name "unconnected-(U$7-ESTIMAT_I2C_SCL-PadP$70)") (class "Default")
      (node (ref "U$7") (pin "P$70") (pinfunction "ESTIMAT_I2C_SCL_P$70") (pintype "bidirectional"))
    )
    (net (code "93") (name "unconnected-(U$7-ESTIMAT_I2C_SDA-PadP$69)") (class "Default")
      (node (ref "U$7") (pin "P$69") (pinfunction "ESTIMAT_I2C_SDA_P$69") (pintype "bidirectional"))
    )
    (net (code "94") (name "unconnected-(U$7-ESTIMAT_VBAT-PadP$77)") (class "Default")
      (node (ref "U$7") (pin "P$77") (pinfunction "ESTIMAT_VBAT_P$77") (pintype "bidirectional"))
    )
    (net (code "95") (name "unconnected-(U$7-ESTIMAT_VBAT-PadP$79)") (class "Default")
      (node (ref "U$7") (pin "P$79") (pinfunction "ESTIMAT_VBAT_P$79") (pintype "bidirectional"))
    )
    (net (code "96") (name "unconnected-(U$7-MAG1_PWM-PadP$73)") (class "Default")
      (node (ref "U$7") (pin "P$73") (pinfunction "MAG1_PWM_P$73") (pintype "bidirectional"))
    )
    (net (code "97") (name "unconnected-(U$7-MAG2_PWM-PadP$74)") (class "Default")
      (node (ref "U$7") (pin "P$74") (pinfunction "MAG2_PWM_P$74") (pintype "bidirectional"))
    )
    (net (code "98") (name "unconnected-(U$7-MAG3_PWM-PadP$75)") (class "Default")
      (node (ref "U$7") (pin "P$75") (pinfunction "MAG3_PWM_P$75") (pintype "bidirectional"))
    )
    (net (code "99") (name "unconnected-(U$7-MCU_GND-PadP$46)") (class "Default")
      (node (ref "U$7") (pin "P$46") (pinfunction "MCU_GND_P$46") (pintype "bidirectional"))
    )
    (net (code "100") (name "unconnected-(U$7-MCU_GND-PadP$47)") (class "Default")
      (node (ref "U$7") (pin "P$47") (pinfunction "MCU_GND_P$47") (pintype "bidirectional"))
    )
    (net (code "101") (name "unconnected-(U$7-MCU_GND-PadP$58)") (class "Default")
      (node (ref "U$7") (pin "P$58") (pinfunction "MCU_GND_P$58") (pintype "bidirectional"))
    )
    (net (code "102") (name "unconnected-(U$7-MCU_GND-PadP$59)") (class "Default")
      (node (ref "U$7") (pin "P$59") (pinfunction "MCU_GND_P$59") (pintype "bidirectional"))
    )
    (net (code "103") (name "unconnected-(U$7-PPT_GND-PadP$1)") (class "Default")
      (node (ref "U$7") (pin "P$1") (pinfunction "PPT_GND_P$1") (pintype "bidirectional"))
    )
    (net (code "104") (name "unconnected-(U$7-PPT_GND-PadP$3)") (class "Default")
      (node (ref "U$7") (pin "P$3") (pinfunction "PPT_GND_P$3") (pintype "bidirectional"))
    )
    (net (code "105") (name "unconnected-(U$7-PPT_GND-PadP$6)") (class "Default")
      (node (ref "U$7") (pin "P$6") (pinfunction "PPT_GND_P$6") (pintype "bidirectional"))
    )
    (net (code "106") (name "unconnected-(U$7-PPT_GND-PadP$8)") (class "Default")
      (node (ref "U$7") (pin "P$8") (pinfunction "PPT_GND_P$8") (pintype "bidirectional"))
    )
    (net (code "107") (name "unconnected-(U$7-PPT_GND-PadP$9)") (class "Default")
      (node (ref "U$7") (pin "P$9") (pinfunction "PPT_GND_P$9") (pintype "bidirectional"))
    )
    (net (code "108") (name "unconnected-(U$7-PPT_GND-PadP$11)") (class "Default")
      (node (ref "U$7") (pin "P$11") (pinfunction "PPT_GND_P$11") (pintype "bidirectional"))
    )
    (net (code "109") (name "unconnected-(U$7-PPT_GND-PadP$14)") (class "Default")
      (node (ref "U$7") (pin "P$14") (pinfunction "PPT_GND_P$14") (pintype "bidirectional"))
    )
    (net (code "110") (name "unconnected-(U$7-PPT_GND-PadP$16)") (class "Default")
      (node (ref "U$7") (pin "P$16") (pinfunction "PPT_GND_P$16") (pintype "bidirectional"))
    )
    (net (code "111") (name "unconnected-(U$7-PPT_VBAT-PadP$2)") (class "Default")
      (node (ref "U$7") (pin "P$2") (pinfunction "PPT_VBAT_P$2") (pintype "bidirectional"))
    )
    (net (code "112") (name "unconnected-(U$7-PPT_VBAT-PadP$4)") (class "Default")
      (node (ref "U$7") (pin "P$4") (pinfunction "PPT_VBAT_P$4") (pintype "bidirectional"))
    )
    (net (code "113") (name "unconnected-(U$7-PPT_VBAT-PadP$5)") (class "Default")
      (node (ref "U$7") (pin "P$5") (pinfunction "PPT_VBAT_P$5") (pintype "bidirectional"))
    )
    (net (code "114") (name "unconnected-(U$7-PPT_VBAT-PadP$7)") (class "Default")
      (node (ref "U$7") (pin "P$7") (pinfunction "PPT_VBAT_P$7") (pintype "bidirectional"))
    )
    (net (code "115") (name "unconnected-(U$7-PPT_VBAT-PadP$10)") (class "Default")
      (node (ref "U$7") (pin "P$10") (pinfunction "PPT_VBAT_P$10") (pintype "bidirectional"))
    )
    (net (code "116") (name "unconnected-(U$7-PPT_VBAT-PadP$12)") (class "Default")
      (node (ref "U$7") (pin "P$12") (pinfunction "PPT_VBAT_P$12") (pintype "bidirectional"))
    )
    (net (code "117") (name "unconnected-(U$7-PPT_VBAT-PadP$13)") (class "Default")
      (node (ref "U$7") (pin "P$13") (pinfunction "PPT_VBAT_P$13") (pintype "bidirectional"))
    )
    (net (code "118") (name "unconnected-(U$7-PPT_VBAT-PadP$15)") (class "Default")
      (node (ref "U$7") (pin "P$15") (pinfunction "PPT_VBAT_P$15") (pintype "bidirectional"))
    )
    (net (code "119") (name "unconnected-(U$7-PadP$36)") (class "Default")
      (node (ref "U$7") (pin "P$36") (pinfunction "P$36_P$36") (pintype "bidirectional"))
    )
    (net (code "120") (name "unconnected-(U$7-PadP$39)") (class "Default")
      (node (ref "U$7") (pin "P$39") (pinfunction "P$39_P$39") (pintype "bidirectional"))
    )
    (net (code "121") (name "unconnected-(U$7-PadP$40)") (class "Default")
      (node (ref "U$7") (pin "P$40") (pinfunction "P$40_P$40") (pintype "bidirectional"))
    )
    (net (code "122") (name "unconnected-(U$7-PadP$43)") (class "Default")
      (node (ref "U$7") (pin "P$43") (pinfunction "P$43_P$43") (pintype "bidirectional"))
    )
    (net (code "123") (name "unconnected-(U$7-PadP$44)") (class "Default")
      (node (ref "U$7") (pin "P$44") (pinfunction "P$44_P$44") (pintype "bidirectional"))
    )
    (net (code "124") (name "unconnected-(U$7-PadP$48)") (class "Default")
      (node (ref "U$7") (pin "P$48") (pinfunction "P$48_P$48") (pintype "bidirectional"))
    )
    (net (code "125") (name "unconnected-(U$7-PadP$52)") (class "Default")
      (node (ref "U$7") (pin "P$52") (pinfunction "P$52_P$52") (pintype "bidirectional"))
    )
    (net (code "126") (name "unconnected-(U$7-PadP$56)") (class "Default")
      (node (ref "U$7") (pin "P$56") (pinfunction "P$56_P$56") (pintype "bidirectional"))
    )
    (net (code "127") (name "unconnected-(U$7-PadP$60)") (class "Default")
      (node (ref "U$7") (pin "P$60") (pinfunction "P$60_P$60") (pintype "bidirectional"))
    )
    (net (code "128") (name "unconnected-(U$7-PadP$61)") (class "Default")
      (node (ref "U$7") (pin "P$61") (pinfunction "P$61_P$61") (pintype "bidirectional"))
    )
    (net (code "129") (name "unconnected-(U$7-PadP$62)") (class "Default")
      (node (ref "U$7") (pin "P$62") (pinfunction "P$62_P$62") (pintype "bidirectional"))
    )
    (net (code "130") (name "unconnected-(U$7-PadP$63)") (class "Default")
      (node (ref "U$7") (pin "P$63") (pinfunction "P$63_P$63") (pintype "bidirectional"))
    )
    (net (code "131") (name "unconnected-(U$7-PadP$64)") (class "Default")
      (node (ref "U$7") (pin "P$64") (pinfunction "P$64_P$64") (pintype "bidirectional"))
    )
    (net (code "132") (name "unconnected-(U$7-PadP$65)") (class "Default")
      (node (ref "U$7") (pin "P$65") (pinfunction "P$65_P$65") (pintype "bidirectional"))
    )
    (net (code "133") (name "unconnected-(U$7-PadP$66)") (class "Default")
      (node (ref "U$7") (pin "P$66") (pinfunction "P$66_P$66") (pintype "bidirectional"))
    )
    (net (code "134") (name "unconnected-(U$7-PadP$67)") (class "Default")
      (node (ref "U$7") (pin "P$67") (pinfunction "P$67_P$67") (pintype "bidirectional"))
    )
    (net (code "135") (name "unconnected-(U$7-PadP$68)") (class "Default")
      (node (ref "U$7") (pin "P$68") (pinfunction "P$68_P$68") (pintype "bidirectional"))
    )
    (net (code "136") (name "unconnected-(U$7-PadP$71)") (class "Default")
      (node (ref "U$7") (pin "P$71") (pinfunction "P$71_P$71") (pintype "bidirectional"))
    )
    (net (code "137") (name "unconnected-(U$7-PadP$72)") (class "Default")
      (node (ref "U$7") (pin "P$72") (pinfunction "P$72_P$72") (pintype "bidirectional"))
    )
    (net (code "138") (name "unconnected-(U$7-PadP$76)") (class "Default")
      (node (ref "U$7") (pin "P$76") (pinfunction "P$76_P$76") (pintype "bidirectional"))
    )
    (net (code "139") (name "unconnected-(U$7-PadP$91)") (class "Default")
      (node (ref "U$7") (pin "P$91") (pinfunction "P$91_P$91") (pintype "bidirectional"))
    )
    (net (code "140") (name "unconnected-(U$7-PadP$92)") (class "Default")
      (node (ref "U$7") (pin "P$92") (pinfunction "P$92_P$92") (pintype "bidirectional"))
    )
    (net (code "141") (name "unconnected-(U$7-PadP$95)") (class "Default")
      (node (ref "U$7") (pin "P$95") (pinfunction "P$95_P$95") (pintype "bidirectional"))
    )
    (net (code "142") (name "unconnected-(U$7-PadP$96)") (class "Default")
      (node (ref "U$7") (pin "P$96") (pinfunction "P$96_P$96") (pintype "bidirectional"))
    )
    (net (code "143") (name "unconnected-(U$7-RAHS_GND-PadP$94)") (class "Default")
      (node (ref "U$7") (pin "P$94") (pinfunction "RAHS_GND_P$94") (pintype "bidirectional"))
    )
    (net (code "144") (name "unconnected-(U$7-RAHS_VBAT-PadP$93)") (class "Default")
      (node (ref "U$7") (pin "P$93") (pinfunction "RAHS_VBAT_P$93") (pintype "bidirectional"))
    )
  )
)
